# CryptoBoard.net
KiCad netlist of a schematic drawn in EAGLE
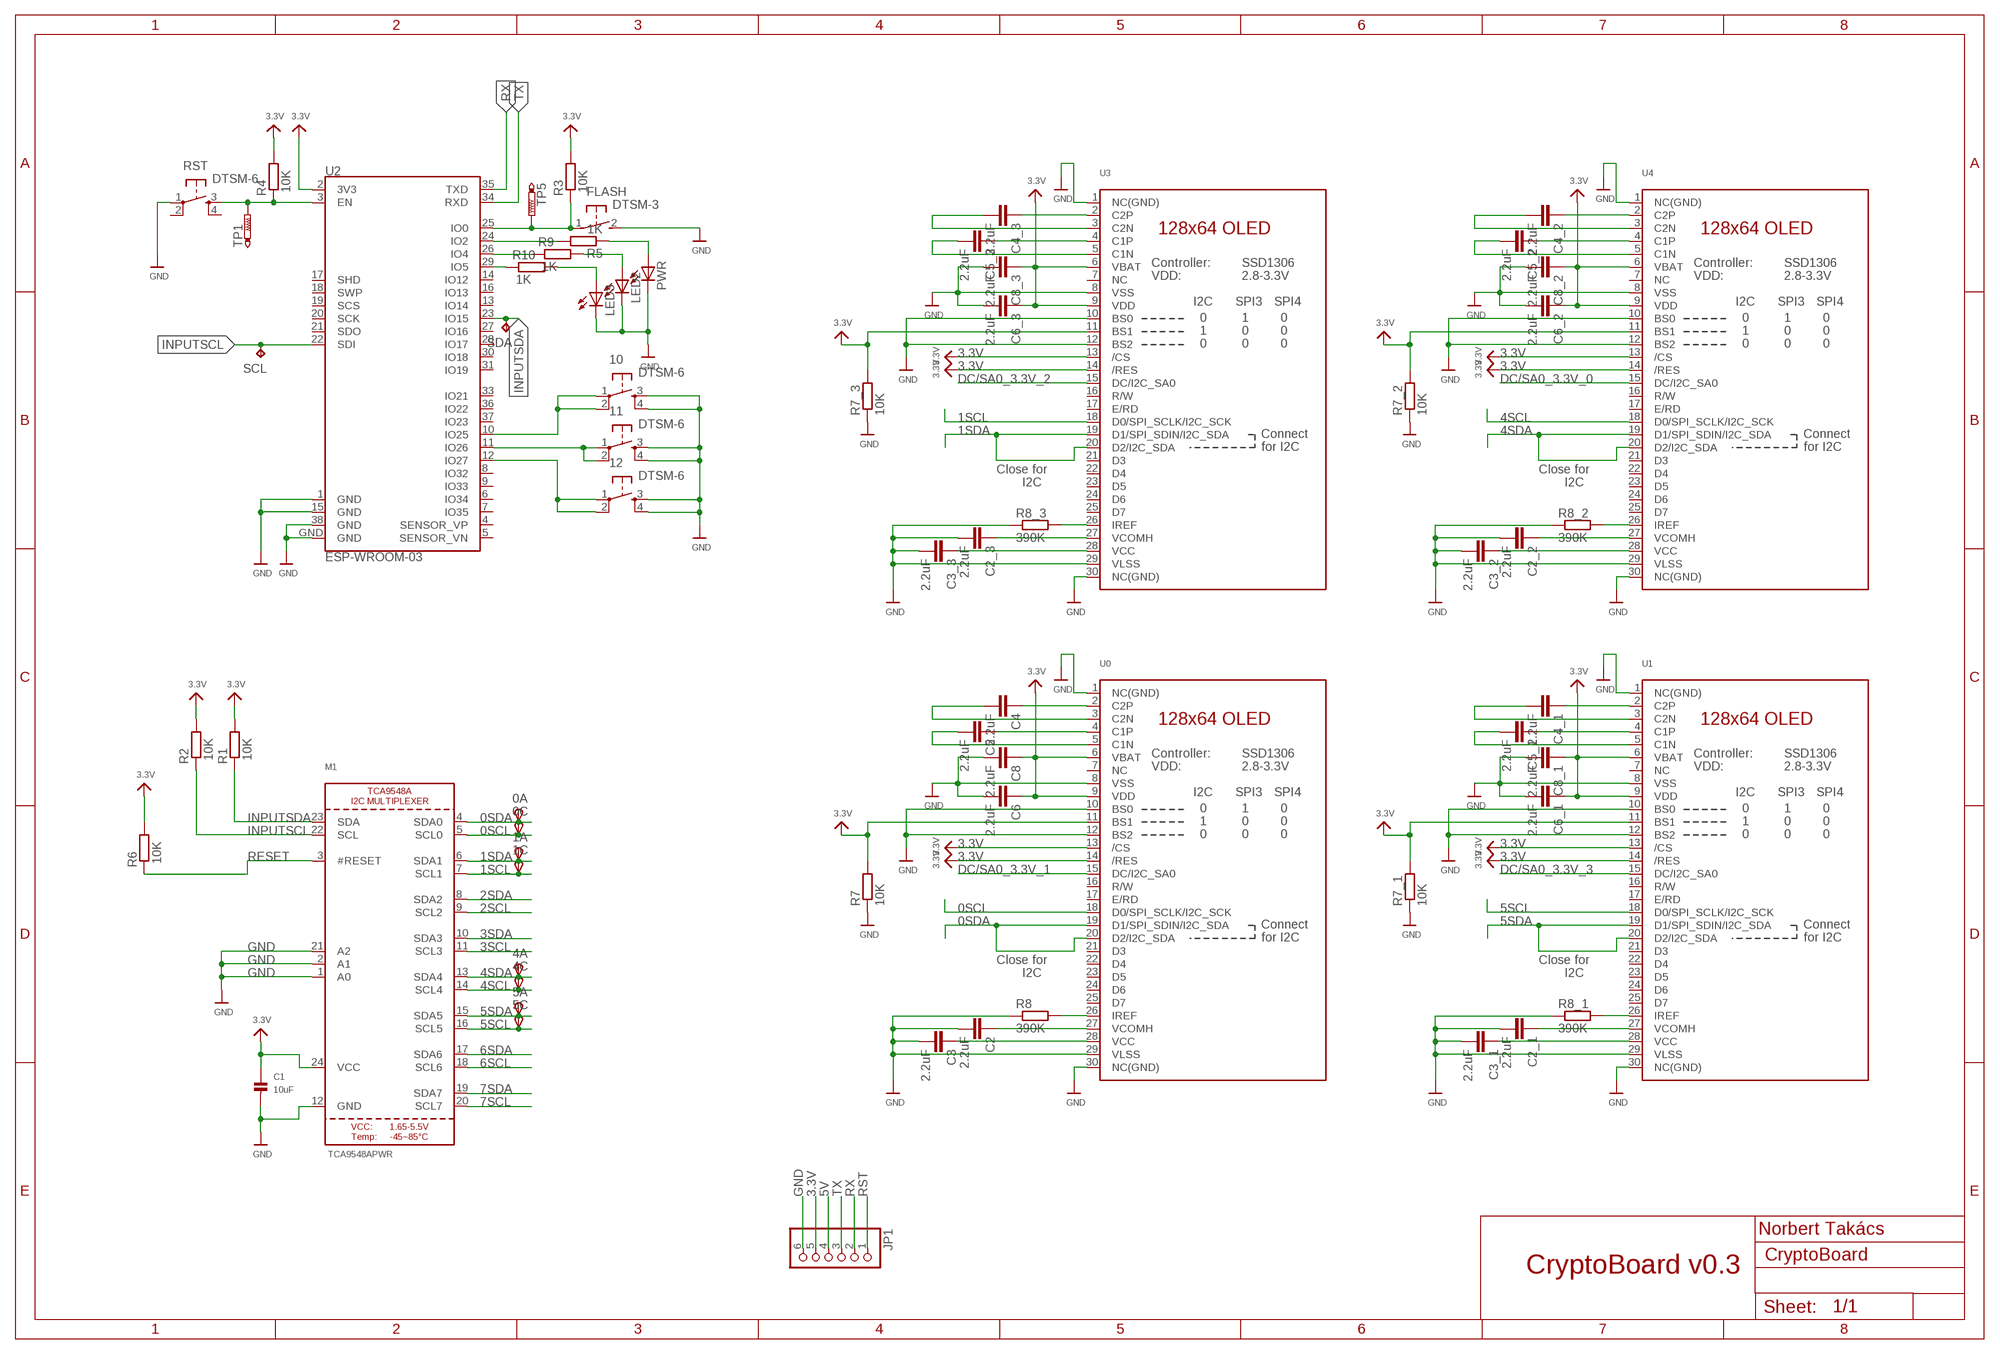
[diagram p0: schematic, sheet 1]

(export (version "E")
  (design (tool "Eeschema 10.0.6"))
  (components
    (comp (ref "0A")
      (value "TPSTP20R")
      (footprint "eagle-import:TP20R")
      (libsource (lib "eagle-import") (part "TPSTP20R"))
    )
    (comp (ref "0C")
      (value "TPSTP20R")
      (footprint "eagle-import:TP20R")
      (libsource (lib "eagle-import") (part "TPSTP20R"))
    )
    (comp (ref "1A")
      (value "TPSTP20R")
      (footprint "eagle-import:TP20R")
      (libsource (lib "eagle-import") (part "TPSTP20R"))
    )
    (comp (ref "1C")
      (value "TPSTP20R")
      (footprint "eagle-import:TP20R")
      (libsource (lib "eagle-import") (part "TPSTP20R"))
    )
    (comp (ref "4A")
      (value "TPSTP20R")
      (footprint "eagle-import:TP20R")
      (libsource (lib "eagle-import") (part "TPSTP20R"))
    )
    (comp (ref "4C")
      (value "TPSTP20R")
      (footprint "eagle-import:TP20R")
      (libsource (lib "eagle-import") (part "TPSTP20R"))
    )
    (comp (ref "5A")
      (value "TPSTP20R")
      (footprint "eagle-import:TP20R")
      (libsource (lib "eagle-import") (part "TPSTP20R"))
    )
    (comp (ref "5C")
      (value "TPSTP20R")
      (footprint "eagle-import:TP20R")
      (libsource (lib "eagle-import") (part "TPSTP20R"))
    )
    (comp (ref "10")
      (value "DTSM-6")
      (footprint "eagle-import:DTSM-6")
      (libsource (lib "eagle-import") (part "DTSM-6"))
    )
    (comp (ref "11")
      (value "DTSM-6")
      (footprint "eagle-import:DTSM-6")
      (libsource (lib "eagle-import") (part "DTSM-6"))
    )
    (comp (ref "12")
      (value "DTSM-6")
      (footprint "eagle-import:DTSM-6")
      (libsource (lib "eagle-import") (part "DTSM-6"))
    )
    (comp (ref "C1")
      (value "10uF")
      (footprint "eagle-import:0805")
      (libsource (lib "eagle-import") (part "CAP_CERAMIC0805"))
    )
    (comp (ref "C2")
      (value "2.2uF")
      (footprint "eagle-import:C0805")
      (libsource (lib "eagle-import") (part "C-EUC0805"))
    )
    (comp (ref "C2_1")
      (value "2.2uF")
      (footprint "eagle-import:C0805")
      (libsource (lib "eagle-import") (part "C-EUC0805"))
    )
    (comp (ref "C2_2")
      (value "2.2uF")
      (footprint "eagle-import:C0805")
      (libsource (lib "eagle-import") (part "C-EUC0805"))
    )
    (comp (ref "C2_3")
      (value "2.2uF")
      (footprint "eagle-import:C0805")
      (libsource (lib "eagle-import") (part "C-EUC0805"))
    )
    (comp (ref "C3")
      (value "2.2uF")
      (footprint "eagle-import:C0805")
      (libsource (lib "eagle-import") (part "C-EUC0805"))
    )
    (comp (ref "C3_1")
      (value "2.2uF")
      (footprint "eagle-import:C0805")
      (libsource (lib "eagle-import") (part "C-EUC0805"))
    )
    (comp (ref "C3_2")
      (value "2.2uF")
      (footprint "eagle-import:C0805")
      (libsource (lib "eagle-import") (part "C-EUC0805"))
    )
    (comp (ref "C3_3")
      (value "2.2uF")
      (footprint "eagle-import:C0805")
      (libsource (lib "eagle-import") (part "C-EUC0805"))
    )
    (comp (ref "C4")
      (value "2.2uF")
      (footprint "eagle-import:C0805")
      (libsource (lib "eagle-import") (part "C-EUC0805"))
    )
    (comp (ref "C4_1")
      (value "2.2uF")
      (footprint "eagle-import:C0805")
      (libsource (lib "eagle-import") (part "C-EUC0805"))
    )
    (comp (ref "C4_2")
      (value "2.2uF")
      (footprint "eagle-import:C0805")
      (libsource (lib "eagle-import") (part "C-EUC0805"))
    )
    (comp (ref "C4_3")
      (value "2.2uF")
      (footprint "eagle-import:C0805")
      (libsource (lib "eagle-import") (part "C-EUC0805"))
    )
    (comp (ref "C5")
      (value "2.2uF")
      (footprint "eagle-import:C0805")
      (libsource (lib "eagle-import") (part "C-EUC0805"))
    )
    (comp (ref "C5_1")
      (value "2.2uF")
      (footprint "eagle-import:C0805")
      (libsource (lib "eagle-import") (part "C-EUC0805"))
    )
    (comp (ref "C5_2")
      (value "2.2uF")
      (footprint "eagle-import:C0805")
      (libsource (lib "eagle-import") (part "C-EUC0805"))
    )
    (comp (ref "C5_3")
      (value "2.2uF")
      (footprint "eagle-import:C0805")
      (libsource (lib "eagle-import") (part "C-EUC0805"))
    )
    (comp (ref "C6")
      (value "2.2uF")
      (footprint "eagle-import:C0805")
      (libsource (lib "eagle-import") (part "C-EUC0805"))
    )
    (comp (ref "C6_1")
      (value "2.2uF")
      (footprint "eagle-import:C0805")
      (libsource (lib "eagle-import") (part "C-EUC0805"))
    )
    (comp (ref "C6_2")
      (value "2.2uF")
      (footprint "eagle-import:C0805")
      (libsource (lib "eagle-import") (part "C-EUC0805"))
    )
    (comp (ref "C6_3")
      (value "2.2uF")
      (footprint "eagle-import:C0805")
      (libsource (lib "eagle-import") (part "C-EUC0805"))
    )
    (comp (ref "C8")
      (value "2.2uF")
      (footprint "eagle-import:C0805")
      (libsource (lib "eagle-import") (part "C-EUC0805"))
    )
    (comp (ref "C8_1")
      (value "2.2uF")
      (footprint "eagle-import:C0805")
      (libsource (lib "eagle-import") (part "C-EUC0805"))
    )
    (comp (ref "C8_2")
      (value "2.2uF")
      (footprint "eagle-import:C0805")
      (libsource (lib "eagle-import") (part "C-EUC0805"))
    )
    (comp (ref "C8_3")
      (value "2.2uF")
      (footprint "eagle-import:C0805")
      (libsource (lib "eagle-import") (part "C-EUC0805"))
    )
    (comp (ref "FLASH")
      (value "DTSM-3")
      (footprint "eagle-import:DTSM-3")
      (libsource (lib "eagle-import") (part "DTSM-3"))
    )
    (comp (ref "JP1")
      (value "PINHD-1X6")
      (footprint "eagle-import:1X06")
      (libsource (lib "eagle-import") (part "PINHD-1X6"))
    )
    (comp (ref "LED2")
      (value "LEDSML0805")
      (footprint "eagle-import:SML0805")
      (libsource (lib "eagle-import") (part "LEDSML0805"))
    )
    (comp (ref "LED3")
      (value "LEDSML0805")
      (footprint "eagle-import:SML0805")
      (libsource (lib "eagle-import") (part "LEDSML0805"))
    )
    (comp (ref "M1")
      (value "TCA9548APWR")
      (footprint "eagle-import:TSSOP24")
      (libsource (lib "eagle-import") (part "TCA9548A"))
    )
    (comp (ref "PWR")
      (value "LEDSML0805")
      (footprint "eagle-import:SML0805")
      (libsource (lib "eagle-import") (part "LEDSML0805"))
    )
    (comp (ref "R1")
      (value "10K")
      (footprint "eagle-import:M0805")
      (libsource (lib "eagle-import") (part "R-EU_M0805"))
    )
    (comp (ref "R2")
      (value "10K")
      (footprint "eagle-import:M0805")
      (libsource (lib "eagle-import") (part "R-EU_M0805"))
    )
    (comp (ref "R3")
      (value "10K")
      (footprint "eagle-import:M0805")
      (libsource (lib "eagle-import") (part "R-EU_M0805"))
    )
    (comp (ref "R4")
      (value "10K")
      (footprint "eagle-import:M0805")
      (libsource (lib "eagle-import") (part "R-EU_M0805"))
    )
    (comp (ref "R5")
      (value "1K")
      (footprint "eagle-import:M0805")
      (libsource (lib "eagle-import") (part "R-EU_M0805"))
    )
    (comp (ref "R6")
      (value "10K")
      (footprint "eagle-import:M0805")
      (libsource (lib "eagle-import") (part "R-EU_M0805"))
    )
    (comp (ref "R7")
      (value "10K")
      (footprint "eagle-import:M0805")
      (libsource (lib "eagle-import") (part "R-EU_M0805"))
    )
    (comp (ref "R7_1")
      (value "10K")
      (footprint "eagle-import:M0805")
      (libsource (lib "eagle-import") (part "R-EU_M0805"))
    )
    (comp (ref "R7_2")
      (value "10K")
      (footprint "eagle-import:M0805")
      (libsource (lib "eagle-import") (part "R-EU_M0805"))
    )
    (comp (ref "R7_3")
      (value "10K")
      (footprint "eagle-import:M0805")
      (libsource (lib "eagle-import") (part "R-EU_M0805"))
    )
    (comp (ref "R8")
      (value "390K")
      (footprint "eagle-import:M0805")
      (libsource (lib "eagle-import") (part "R-EU_M0805"))
    )
    (comp (ref "R8_1")
      (value "390K")
      (footprint "eagle-import:M0805")
      (libsource (lib "eagle-import") (part "R-EU_M0805"))
    )
    (comp (ref "R8_2")
      (value "390K")
      (footprint "eagle-import:M0805")
      (libsource (lib "eagle-import") (part "R-EU_M0805"))
    )
    (comp (ref "R8_3")
      (value "390K")
      (footprint "eagle-import:M0805")
      (libsource (lib "eagle-import") (part "R-EU_M0805"))
    )
    (comp (ref "R9")
      (value "1K")
      (footprint "eagle-import:M0805")
      (libsource (lib "eagle-import") (part "R-EU_M0805"))
    )
    (comp (ref "R10")
      (value "1K")
      (footprint "eagle-import:M0805")
      (libsource (lib "eagle-import") (part "R-EU_M0805"))
    )
    (comp (ref "RST")
      (value "DTSM-6")
      (footprint "eagle-import:DTSM-6")
      (libsource (lib "eagle-import") (part "DTSM-6"))
    )
    (comp (ref "SCL")
      (value "TPPAD1-13")
      (footprint "eagle-import:P1-13")
      (libsource (lib "eagle-import") (part "TPPAD1-13"))
    )
    (comp (ref "SDA")
      (value "TPPAD1-13")
      (footprint "eagle-import:P1-13")
      (libsource (lib "eagle-import") (part "TPPAD1-13"))
    )
    (comp (ref "TP1")
      (value "PTR1B2,54")
      (footprint "eagle-import:B2,54")
      (libsource (lib "eagle-import") (part "PTR1B2,54"))
    )
    (comp (ref "TP5")
      (value "PTR1B2,54")
      (footprint "eagle-import:B2,54")
      (libsource (lib "eagle-import") (part "PTR1B2,54"))
    )
    (comp (ref "U0")
      (value "DISP_OLED_UG-2864HSWEG01")
      (footprint "eagle-import:UG-2864HSWEG01_1.3_WRAPAROUND")
      (libsource (lib "eagle-import") (part "DISP_OLED_UG-2864HSWEG01"))
    )
    (comp (ref "U1")
      (value "DISP_OLED_UG-2864HSWEG01")
      (footprint "eagle-import:UG-2864HSWEG01_1.3_WRAPAROUND")
      (libsource (lib "eagle-import") (part "DISP_OLED_UG-2864HSWEG01"))
    )
    (comp (ref "U2")
      (value "ESP-WROOM-03")
      (footprint "eagle-import:ESP-WROOM-03")
      (libsource (lib "eagle-import") (part "ESP-WROOM-03"))
    )
    (comp (ref "U3")
      (value "DISP_OLED_UG-2864HSWEG01")
      (footprint "eagle-import:UG-2864HSWEG01_1.3_WRAPAROUND")
      (libsource (lib "eagle-import") (part "DISP_OLED_UG-2864HSWEG01"))
    )
    (comp (ref "U4")
      (value "DISP_OLED_UG-2864HSWEG01")
      (footprint "eagle-import:UG-2864HSWEG01_1.3_WRAPAROUND")
      (libsource (lib "eagle-import") (part "DISP_OLED_UG-2864HSWEG01"))
    )
  )
  (nets
    (net (code "1") (name "/0SCL") (class "Default")
      (node (ref "0C") (pin "TP") (pinfunction "PP_TP") (pintype "input"))
      (node (ref "M1") (pin "5") (pinfunction "SCL0_5") (pintype "bidirectional"))
      (node (ref "U0") (pin "18") (pinfunction "D0/SPI_SCLK/I2C_SCK_18") (pintype "bidirectional"))
    )
    (net (code "2") (name "/0SDA") (class "Default")
      (node (ref "0A") (pin "TP") (pinfunction "PP_TP") (pintype "input"))
      (node (ref "M1") (pin "4") (pinfunction "SDA0_4") (pintype "bidirectional"))
      (node (ref "U0") (pin "19") (pinfunction "D1/SPI_SDIN/I2C_SDA_19") (pintype "bidirectional"))
      (node (ref "U0") (pin "20") (pinfunction "D2/I2C_SDA_20") (pintype "bidirectional"))
    )
    (net (code "3") (name "/1SCL") (class "Default")
      (node (ref "1C") (pin "TP") (pinfunction "PP_TP") (pintype "input"))
      (node (ref "M1") (pin "7") (pinfunction "SCL1_7") (pintype "bidirectional"))
      (node (ref "U3") (pin "18") (pinfunction "D0/SPI_SCLK/I2C_SCK_18") (pintype "bidirectional"))
    )
    (net (code "4") (name "/1SDA") (class "Default")
      (node (ref "1A") (pin "TP") (pinfunction "PP_TP") (pintype "input"))
      (node (ref "M1") (pin "6") (pinfunction "SDA1_6") (pintype "bidirectional"))
      (node (ref "U3") (pin "19") (pinfunction "D1/SPI_SDIN/I2C_SDA_19") (pintype "bidirectional"))
      (node (ref "U3") (pin "20") (pinfunction "D2/I2C_SDA_20") (pintype "bidirectional"))
    )
    (net (code "5") (name "/2SCL") (class "Default")
      (node (ref "M1") (pin "9") (pinfunction "SCL2_9") (pintype "bidirectional"))
    )
    (net (code "6") (name "/2SDA") (class "Default")
      (node (ref "M1") (pin "8") (pinfunction "SDA2_8") (pintype "bidirectional"))
    )
    (net (code "7") (name "/3SCL") (class "Default")
      (node (ref "M1") (pin "11") (pinfunction "SCL3_11") (pintype "bidirectional"))
    )
    (net (code "8") (name "/3SDA") (class "Default")
      (node (ref "M1") (pin "10") (pinfunction "SDA3_10") (pintype "bidirectional"))
    )
    (net (code "9") (name "/4SCL") (class "Default")
      (node (ref "4C") (pin "TP") (pinfunction "PP_TP") (pintype "input"))
      (node (ref "M1") (pin "14") (pinfunction "SCL4_14") (pintype "bidirectional"))
      (node (ref "U4") (pin "18") (pinfunction "D0/SPI_SCLK/I2C_SCK_18") (pintype "bidirectional"))
    )
    (net (code "10") (name "/4SDA") (class "Default")
      (node (ref "4A") (pin "TP") (pinfunction "PP_TP") (pintype "input"))
      (node (ref "M1") (pin "13") (pinfunction "SDA4_13") (pintype "bidirectional"))
      (node (ref "U4") (pin "19") (pinfunction "D1/SPI_SDIN/I2C_SDA_19") (pintype "bidirectional"))
      (node (ref "U4") (pin "20") (pinfunction "D2/I2C_SDA_20") (pintype "bidirectional"))
    )
    (net (code "11") (name "/5SCL") (class "Default")
      (node (ref "5C") (pin "TP") (pinfunction "PP_TP") (pintype "input"))
      (node (ref "M1") (pin "16") (pinfunction "SCL5_16") (pintype "bidirectional"))
      (node (ref "U1") (pin "18") (pinfunction "D0/SPI_SCLK/I2C_SCK_18") (pintype "bidirectional"))
    )
    (net (code "12") (name "/5SDA") (class "Default")
      (node (ref "5A") (pin "TP") (pinfunction "PP_TP") (pintype "input"))
      (node (ref "M1") (pin "15") (pinfunction "SDA5_15") (pintype "bidirectional"))
      (node (ref "U1") (pin "19") (pinfunction "D1/SPI_SDIN/I2C_SDA_19") (pintype "bidirectional"))
      (node (ref "U1") (pin "20") (pinfunction "D2/I2C_SDA_20") (pintype "bidirectional"))
    )
    (net (code "13") (name "/5V") (class "Default")
      (node (ref "JP1") (pin "4") (pinfunction "4_4") (pintype "passive"))
    )
    (net (code "14") (name "/6SCL") (class "Default")
      (node (ref "M1") (pin "18") (pinfunction "SCL6_18") (pintype "bidirectional"))
    )
    (net (code "15") (name "/6SDA") (class "Default")
      (node (ref "M1") (pin "17") (pinfunction "SDA6_17") (pintype "bidirectional"))
    )
    (net (code "16") (name "/7SCL") (class "Default")
      (node (ref "M1") (pin "20") (pinfunction "SCL7_20") (pintype "bidirectional"))
    )
    (net (code "17") (name "/7SDA") (class "Default")
      (node (ref "M1") (pin "19") (pinfunction "SDA7_19") (pintype "bidirectional"))
    )
    (net (code "18") (name "/DC{slash}SA0_3.3V_0") (class "Default")
      (node (ref "U4") (pin "15") (pinfunction "DC/I2C_SA0_15") (pintype "input"))
    )
    (net (code "19") (name "/DC{slash}SA0_3.3V_1") (class "Default")
      (node (ref "U0") (pin "15") (pinfunction "DC/I2C_SA0_15") (pintype "input"))
    )
    (net (code "20") (name "/DC{slash}SA0_3.3V_2") (class "Default")
      (node (ref "U3") (pin "15") (pinfunction "DC/I2C_SA0_15") (pintype "input"))
    )
    (net (code "21") (name "/DC{slash}SA0_3.3V_3") (class "Default")
      (node (ref "U1") (pin "15") (pinfunction "DC/I2C_SA0_15") (pintype "input"))
    )
    (net (code "22") (name "/RESET") (class "Default")
      (node (ref "M1") (pin "3") (pinfunction "#RESET_3") (pintype "bidirectional"))
      (node (ref "R6") (pin "1") (pinfunction "1_1") (pintype "passive"))
    )
    (net (code "23") (name "/RST") (class "Default")
      (node (ref "JP1") (pin "1") (pinfunction "1_1") (pintype "passive"))
    )
    (net (code "24") (name "3.3V") (class "Default")
      (node (ref "C1") (pin "1") (pinfunction "P$1_1") (pintype "passive"))
      (node (ref "C6") (pin "1") (pinfunction "1_1") (pintype "passive"))
      (node (ref "C6_1") (pin "1") (pinfunction "1_1") (pintype "passive"))
      (node (ref "C6_2") (pin "1") (pinfunction "1_1") (pintype "passive"))
      (node (ref "C6_3") (pin "1") (pinfunction "1_1") (pintype "passive"))
      (node (ref "C8") (pin "1") (pinfunction "1_1") (pintype "passive"))
      (node (ref "C8_1") (pin "1") (pinfunction "1_1") (pintype "passive"))
      (node (ref "C8_2") (pin "1") (pinfunction "1_1") (pintype "passive"))
      (node (ref "C8_3") (pin "1") (pinfunction "1_1") (pintype "passive"))
      (node (ref "JP1") (pin "5") (pinfunction "5_5") (pintype "passive"))
      (node (ref "M1") (pin "24") (pinfunction "VCC_24") (pintype "bidirectional"))
      (node (ref "R1") (pin "2") (pinfunction "2_2") (pintype "passive"))
      (node (ref "R2") (pin "2") (pinfunction "2_2") (pintype "passive"))
      (node (ref "R3") (pin "2") (pinfunction "2_2") (pintype "passive"))
      (node (ref "R4") (pin "2") (pinfunction "2_2") (pintype "passive"))
      (node (ref "R6") (pin "2") (pinfunction "2_2") (pintype "passive"))
      (node (ref "R7") (pin "2") (pinfunction "2_2") (pintype "passive"))
      (node (ref "R7_1") (pin "2") (pinfunction "2_2") (pintype "passive"))
      (node (ref "R7_2") (pin "2") (pinfunction "2_2") (pintype "passive"))
      (node (ref "R7_3") (pin "2") (pinfunction "2_2") (pintype "passive"))
      (node (ref "U0") (pin "11") (pinfunction "BS1_11") (pintype "input"))
      (node (ref "U0") (pin "13") (pinfunction "/CS_13") (pintype "input"))
      (node (ref "U0") (pin "14") (pinfunction "/RES_14") (pintype "input"))
      (node (ref "U0") (pin "6") (pinfunction "VBAT_6") (pintype "input"))
      (node (ref "U0") (pin "9") (pinfunction "VDD_9") (pintype "power_in"))
      (node (ref "U1") (pin "11") (pinfunction "BS1_11") (pintype "input"))
      (node (ref "U1") (pin "13") (pinfunction "/CS_13") (pintype "input"))
      (node (ref "U1") (pin "14") (pinfunction "/RES_14") (pintype "input"))
      (node (ref "U1") (pin "6") (pinfunction "VBAT_6") (pintype "input"))
      (node (ref "U1") (pin "9") (pinfunction "VDD_9") (pintype "power_in"))
      (node (ref "U2") (pin "2") (pinfunction "3V3_2") (pintype "bidirectional"))
      (node (ref "U3") (pin "11") (pinfunction "BS1_11") (pintype "input"))
      (node (ref "U3") (pin "13") (pinfunction "/CS_13") (pintype "input"))
      (node (ref "U3") (pin "14") (pinfunction "/RES_14") (pintype "input"))
      (node (ref "U3") (pin "6") (pinfunction "VBAT_6") (pintype "input"))
      (node (ref "U3") (pin "9") (pinfunction "VDD_9") (pintype "power_in"))
      (node (ref "U4") (pin "11") (pinfunction "BS1_11") (pintype "input"))
      (node (ref "U4") (pin "13") (pinfunction "/CS_13") (pintype "input"))
      (node (ref "U4") (pin "14") (pinfunction "/RES_14") (pintype "input"))
      (node (ref "U4") (pin "6") (pinfunction "VBAT_6") (pintype "input"))
      (node (ref "U4") (pin "9") (pinfunction "VDD_9") (pintype "power_in"))
    )
    (net (code "25") (name "GND") (class "Default")
      (node (ref "10") (pin "3") (pinfunction "3_3") (pintype "passive"))
      (node (ref "10") (pin "4") (pinfunction "4_4") (pintype "passive"))
      (node (ref "11") (pin "3") (pinfunction "3_3") (pintype "passive"))
      (node (ref "11") (pin "4") (pinfunction "4_4") (pintype "passive"))
      (node (ref "12") (pin "3") (pinfunction "3_3") (pintype "passive"))
      (node (ref "12") (pin "4") (pinfunction "4_4") (pintype "passive"))
      (node (ref "C1") (pin "2") (pinfunction "P$2_2") (pintype "passive"))
      (node (ref "C2") (pin "2") (pinfunction "2_2") (pintype "passive"))
      (node (ref "C2_1") (pin "2") (pinfunction "2_2") (pintype "passive"))
      (node (ref "C2_2") (pin "2") (pinfunction "2_2") (pintype "passive"))
      (node (ref "C2_3") (pin "2") (pinfunction "2_2") (pintype "passive"))
      (node (ref "C3") (pin "2") (pinfunction "2_2") (pintype "passive"))
      (node (ref "C3_1") (pin "2") (pinfunction "2_2") (pintype "passive"))
      (node (ref "C3_2") (pin "2") (pinfunction "2_2") (pintype "passive"))
      (node (ref "C3_3") (pin "2") (pinfunction "2_2") (pintype "passive"))
      (node (ref "C6") (pin "2") (pinfunction "2_2") (pintype "passive"))
      (node (ref "C6_1") (pin "2") (pinfunction "2_2") (pintype "passive"))
      (node (ref "C6_2") (pin "2") (pinfunction "2_2") (pintype "passive"))
      (node (ref "C6_3") (pin "2") (pinfunction "2_2") (pintype "passive"))
      (node (ref "C8") (pin "2") (pinfunction "2_2") (pintype "passive"))
      (node (ref "C8_1") (pin "2") (pinfunction "2_2") (pintype "passive"))
      (node (ref "C8_2") (pin "2") (pinfunction "2_2") (pintype "passive"))
      (node (ref "C8_3") (pin "2") (pinfunction "2_2") (pintype "passive"))
      (node (ref "FLASH") (pin "2") (pinfunction "2_2") (pintype "passive"))
      (node (ref "JP1") (pin "6") (pinfunction "6_6") (pintype "passive"))
      (node (ref "LED2") (pin "C") (pinfunction "C_C") (pintype "passive"))
      (node (ref "LED3") (pin "C") (pinfunction "C_C") (pintype "passive"))
      (node (ref "M1") (pin "1") (pinfunction "A0_1") (pintype "bidirectional"))
      (node (ref "M1") (pin "12") (pinfunction "GND_12") (pintype "bidirectional"))
      (node (ref "M1") (pin "2") (pinfunction "A1_2") (pintype "bidirectional"))
      (node (ref "M1") (pin "21") (pinfunction "A2_21") (pintype "bidirectional"))
      (node (ref "PWR") (pin "C") (pinfunction "C_C") (pintype "passive"))
      (node (ref "R7") (pin "1") (pinfunction "1_1") (pintype "passive"))
      (node (ref "R7_1") (pin "1") (pinfunction "1_1") (pintype "passive"))
      (node (ref "R7_2") (pin "1") (pinfunction "1_1") (pintype "passive"))
      (node (ref "R7_3") (pin "1") (pinfunction "1_1") (pintype "passive"))
      (node (ref "R8") (pin "1") (pinfunction "1_1") (pintype "passive"))
      (node (ref "R8_1") (pin "1") (pinfunction "1_1") (pintype "passive"))
      (node (ref "R8_2") (pin "1") (pinfunction "1_1") (pintype "passive"))
      (node (ref "R8_3") (pin "1") (pinfunction "1_1") (pintype "passive"))
      (node (ref "RST") (pin "1") (pinfunction "1_1") (pintype "passive"))
      (node (ref "U0") (pin "1") (pinfunction "NC(GND)_1") (pintype "input"))
      (node (ref "U0") (pin "10") (pinfunction "BS0_10") (pintype "input"))
      (node (ref "U0") (pin "12") (pinfunction "BS2_12") (pintype "input"))
      (node (ref "U0") (pin "29") (pinfunction "VLSS_29") (pintype "power_in"))
      (node (ref "U0") (pin "30") (pinfunction "NC(GND)_30") (pintype "input"))
      (node (ref "U0") (pin "8") (pinfunction "VSS_8") (pintype "power_in"))
      (node (ref "U1") (pin "1") (pinfunction "NC(GND)_1") (pintype "input"))
      (node (ref "U1") (pin "10") (pinfunction "BS0_10") (pintype "input"))
      (node (ref "U1") (pin "12") (pinfunction "BS2_12") (pintype "input"))
      (node (ref "U1") (pin "29") (pinfunction "VLSS_29") (pintype "power_in"))
      (node (ref "U1") (pin "30") (pinfunction "NC(GND)_30") (pintype "input"))
      (node (ref "U1") (pin "8") (pinfunction "VSS_8") (pintype "power_in"))
      (node (ref "U2") (pin "1") (pinfunction "GND_1") (pintype "bidirectional"))
      (node (ref "U2") (pin "15") (pinfunction "GND_15") (pintype "bidirectional"))
      (node (ref "U2") (pin "38") (pinfunction "GND_38") (pintype "bidirectional"))
      (node (ref "U2") (pin "GND") (pinfunction "GND_GND") (pintype "bidirectional"))
      (node (ref "U3") (pin "1") (pinfunction "NC(GND)_1") (pintype "input"))
      (node (ref "U3") (pin "10") (pinfunction "BS0_10") (pintype "input"))
      (node (ref "U3") (pin "12") (pinfunction "BS2_12") (pintype "input"))
      (node (ref "U3") (pin "29") (pinfunction "VLSS_29") (pintype "power_in"))
      (node (ref "U3") (pin "30") (pinfunction "NC(GND)_30") (pintype "input"))
      (node (ref "U3") (pin "8") (pinfunction "VSS_8") (pintype "power_in"))
      (node (ref "U4") (pin "1") (pinfunction "NC(GND)_1") (pintype "input"))
      (node (ref "U4") (pin "10") (pinfunction "BS0_10") (pintype "input"))
      (node (ref "U4") (pin "12") (pinfunction "BS2_12") (pintype "input"))
      (node (ref "U4") (pin "29") (pinfunction "VLSS_29") (pintype "power_in"))
      (node (ref "U4") (pin "30") (pinfunction "NC(GND)_30") (pintype "input"))
      (node (ref "U4") (pin "8") (pinfunction "VSS_8") (pintype "power_in"))
    )
    (net (code "26") (name "INPUTSCL") (class "Default")
      (node (ref "M1") (pin "22") (pinfunction "SCL_22") (pintype "bidirectional"))
      (node (ref "R2") (pin "1") (pinfunction "1_1") (pintype "passive"))
      (node (ref "SCL") (pin "TP") (pinfunction "TP_TP") (pintype "input"))
      (node (ref "U2") (pin "22") (pinfunction "SDI_22") (pintype "bidirectional"))
    )
    (net (code "27") (name "INPUTSDA") (class "Default")
      (node (ref "M1") (pin "23") (pinfunction "SDA_23") (pintype "bidirectional"))
      (node (ref "R1") (pin "1") (pinfunction "1_1") (pintype "passive"))
      (node (ref "SDA") (pin "TP") (pinfunction "TP_TP") (pintype "input"))
      (node (ref "U2") (pin "23") (pinfunction "IO15_23") (pintype "bidirectional"))
    )
    (net (code "28") (name "Net-(LED2-PadA)") (class "Default")
      (node (ref "LED2") (pin "A") (pinfunction "A_A") (pintype "passive"))
      (node (ref "R9") (pin "2") (pinfunction "2_2") (pintype "passive"))
    )
    (net (code "29") (name "Net-(LED3-PadA)") (class "Default")
      (node (ref "LED3") (pin "A") (pinfunction "A_A") (pintype "passive"))
      (node (ref "R10") (pin "2") (pinfunction "2_2") (pintype "passive"))
    )
    (net (code "30") (name "Net-(PWR-PadA)") (class "Default")
      (node (ref "PWR") (pin "A") (pinfunction "A_A") (pintype "passive"))
      (node (ref "R5") (pin "1") (pinfunction "1_1") (pintype "passive"))
    )
    (net (code "31") (name "Net-(U0-C1N)") (class "Default")
      (node (ref "C5") (pin "2") (pinfunction "2_2") (pintype "passive"))
      (node (ref "U0") (pin "5") (pinfunction "C1N_5") (pintype "input"))
    )
    (net (code "32") (name "Net-(U0-C1P)") (class "Default")
      (node (ref "C5") (pin "1") (pinfunction "1_1") (pintype "passive"))
      (node (ref "U0") (pin "4") (pinfunction "C1P_4") (pintype "input"))
    )
    (net (code "33") (name "Net-(U0-C2N)") (class "Default")
      (node (ref "C4") (pin "2") (pinfunction "2_2") (pintype "passive"))
      (node (ref "U0") (pin "3") (pinfunction "C2N_3") (pintype "input"))
    )
    (net (code "34") (name "Net-(U0-C2P)") (class "Default")
      (node (ref "C4") (pin "1") (pinfunction "1_1") (pintype "passive"))
      (node (ref "U0") (pin "2") (pinfunction "C2P_2") (pintype "input"))
    )
    (net (code "35") (name "Net-(U0-IREF)") (class "Default")
      (node (ref "R8") (pin "2") (pinfunction "2_2") (pintype "passive"))
      (node (ref "U0") (pin "26") (pinfunction "IREF_26") (pintype "input"))
    )
    (net (code "36") (name "Net-(U0-VCC)") (class "Default")
      (node (ref "C3") (pin "1") (pinfunction "1_1") (pintype "passive"))
      (node (ref "U0") (pin "28") (pinfunction "VCC_28") (pintype "power_in"))
    )
    (net (code "37") (name "Net-(U0-VCOMH)") (class "Default")
      (node (ref "C2") (pin "1") (pinfunction "1_1") (pintype "passive"))
      (node (ref "U0") (pin "27") (pinfunction "VCOMH_27") (pintype "output"))
    )
    (net (code "38") (name "Net-(U1-C1N)") (class "Default")
      (node (ref "C5_1") (pin "2") (pinfunction "2_2") (pintype "passive"))
      (node (ref "U1") (pin "5") (pinfunction "C1N_5") (pintype "input"))
    )
    (net (code "39") (name "Net-(U1-C1P)") (class "Default")
      (node (ref "C5_1") (pin "1") (pinfunction "1_1") (pintype "passive"))
      (node (ref "U1") (pin "4") (pinfunction "C1P_4") (pintype "input"))
    )
    (net (code "40") (name "Net-(U1-C2N)") (class "Default")
      (node (ref "C4_1") (pin "2") (pinfunction "2_2") (pintype "passive"))
      (node (ref "U1") (pin "3") (pinfunction "C2N_3") (pintype "input"))
    )
    (net (code "41") (name "Net-(U1-C2P)") (class "Default")
      (node (ref "C4_1") (pin "1") (pinfunction "1_1") (pintype "passive"))
      (node (ref "U1") (pin "2") (pinfunction "C2P_2") (pintype "input"))
    )
    (net (code "42") (name "Net-(U1-IREF)") (class "Default")
      (node (ref "R8_1") (pin "2") (pinfunction "2_2") (pintype "passive"))
      (node (ref "U1") (pin "26") (pinfunction "IREF_26") (pintype "input"))
    )
    (net (code "43") (name "Net-(U1-VCC)") (class "Default")
      (node (ref "C3_1") (pin "1") (pinfunction "1_1") (pintype "passive"))
      (node (ref "U1") (pin "28") (pinfunction "VCC_28") (pintype "power_in"))
    )
    (net (code "44") (name "Net-(U1-VCOMH)") (class "Default")
      (node (ref "C2_1") (pin "1") (pinfunction "1_1") (pintype "passive"))
      (node (ref "U1") (pin "27") (pinfunction "VCOMH_27") (pintype "output"))
    )
    (net (code "45") (name "Net-(U2-EN)") (class "Default")
      (node (ref "R4") (pin "1") (pinfunction "1_1") (pintype "passive"))
      (node (ref "RST") (pin "3") (pinfunction "3_3") (pintype "passive"))
      (node (ref "TP1") (pin "TP") (pinfunction "TP_TP") (pintype "input"))
      (node (ref "U2") (pin "3") (pinfunction "EN_3") (pintype "bidirectional"))
    )
    (net (code "46") (name "Net-(U2-IO0)") (class "Default")
      (node (ref "FLASH") (pin "1") (pinfunction "1_1") (pintype "passive"))
      (node (ref "R3") (pin "1") (pinfunction "1_1") (pintype "passive"))
      (node (ref "TP5") (pin "TP") (pinfunction "TP_TP") (pintype "input"))
      (node (ref "U2") (pin "25") (pinfunction "IO0_25") (pintype "bidirectional"))
    )
    (net (code "47") (name "Net-(U2-IO2)") (class "Default")
      (node (ref "R5") (pin "2") (pinfunction "2_2") (pintype "passive"))
      (node (ref "U2") (pin "24") (pinfunction "IO2_24") (pintype "bidirectional"))
    )
    (net (code "48") (name "Net-(U2-IO4)") (class "Default")
      (node (ref "R9") (pin "1") (pinfunction "1_1") (pintype "passive"))
      (node (ref "U2") (pin "26") (pinfunction "IO4_26") (pintype "bidirectional"))
    )
    (net (code "49") (name "Net-(U2-IO5)") (class "Default")
      (node (ref "R10") (pin "1") (pinfunction "1_1") (pintype "passive"))
      (node (ref "U2") (pin "29") (pinfunction "IO5_29") (pintype "bidirectional"))
    )
    (net (code "50") (name "Net-(U2-IO25)") (class "Default")
      (node (ref "10") (pin "1") (pinfunction "1_1") (pintype "passive"))
      (node (ref "10") (pin "2") (pinfunction "2_2") (pintype "passive"))
      (node (ref "U2") (pin "10") (pinfunction "IO25_10") (pintype "bidirectional"))
    )
    (net (code "51") (name "Net-(U2-IO26)") (class "Default")
      (node (ref "11") (pin "1") (pinfunction "1_1") (pintype "passive"))
      (node (ref "11") (pin "2") (pinfunction "2_2") (pintype "passive"))
      (node (ref "U2") (pin "11") (pinfunction "IO26_11") (pintype "bidirectional"))
    )
    (net (code "52") (name "Net-(U2-IO27)") (class "Default")
      (node (ref "12") (pin "1") (pinfunction "1_1") (pintype "passive"))
      (node (ref "12") (pin "2") (pinfunction "2_2") (pintype "passive"))
      (node (ref "U2") (pin "12") (pinfunction "IO27_12") (pintype "bidirectional"))
    )
    (net (code "53") (name "Net-(U3-C1N)") (class "Default")
      (node (ref "C5_3") (pin "2") (pinfunction "2_2") (pintype "passive"))
      (node (ref "U3") (pin "5") (pinfunction "C1N_5") (pintype "input"))
    )
    (net (code "54") (name "Net-(U3-C1P)") (class "Default")
      (node (ref "C5_3") (pin "1") (pinfunction "1_1") (pintype "passive"))
      (node (ref "U3") (pin "4") (pinfunction "C1P_4") (pintype "input"))
    )
    (net (code "55") (name "Net-(U3-C2N)") (class "Default")
      (node (ref "C4_3") (pin "2") (pinfunction "2_2") (pintype "passive"))
      (node (ref "U3") (pin "3") (pinfunction "C2N_3") (pintype "input"))
    )
    (net (code "56") (name "Net-(U3-C2P)") (class "Default")
      (node (ref "C4_3") (pin "1") (pinfunction "1_1") (pintype "passive"))
      (node (ref "U3") (pin "2") (pinfunction "C2P_2") (pintype "input"))
    )
    (net (code "57") (name "Net-(U3-IREF)") (class "Default")
      (node (ref "R8_3") (pin "2") (pinfunction "2_2") (pintype "passive"))
      (node (ref "U3") (pin "26") (pinfunction "IREF_26") (pintype "input"))
    )
    (net (code "58") (name "Net-(U3-VCC)") (class "Default")
      (node (ref "C3_3") (pin "1") (pinfunction "1_1") (pintype "passive"))
      (node (ref "U3") (pin "28") (pinfunction "VCC_28") (pintype "power_in"))
    )
    (net (code "59") (name "Net-(U3-VCOMH)") (class "Default")
      (node (ref "C2_3") (pin "1") (pinfunction "1_1") (pintype "passive"))
      (node (ref "U3") (pin "27") (pinfunction "VCOMH_27") (pintype "output"))
    )
    (net (code "60") (name "Net-(U4-C1N)") (class "Default")
      (node (ref "C5_2") (pin "2") (pinfunction "2_2") (pintype "passive"))
      (node (ref "U4") (pin "5") (pinfunction "C1N_5") (pintype "input"))
    )
    (net (code "61") (name "Net-(U4-C1P)") (class "Default")
      (node (ref "C5_2") (pin "1") (pinfunction "1_1") (pintype "passive"))
      (node (ref "U4") (pin "4") (pinfunction "C1P_4") (pintype "input"))
    )
    (net (code "62") (name "Net-(U4-C2N)") (class "Default")
      (node (ref "C4_2") (pin "2") (pinfunction "2_2") (pintype "passive"))
      (node (ref "U4") (pin "3") (pinfunction "C2N_3") (pintype "input"))
    )
    (net (code "63") (name "Net-(U4-C2P)") (class "Default")
      (node (ref "C4_2") (pin "1") (pinfunction "1_1") (pintype "passive"))
      (node (ref "U4") (pin "2") (pinfunction "C2P_2") (pintype "input"))
    )
    (net (code "64") (name "Net-(U4-IREF)") (class "Default")
      (node (ref "R8_2") (pin "2") (pinfunction "2_2") (pintype "passive"))
      (node (ref "U4") (pin "26") (pinfunction "IREF_26") (pintype "input"))
    )
    (net (code "65") (name "Net-(U4-VCC)") (class "Default")
      (node (ref "C3_2") (pin "1") (pinfunction "1_1") (pintype "passive"))
      (node (ref "U4") (pin "28") (pinfunction "VCC_28") (pintype "power_in"))
    )
    (net (code "66") (name "Net-(U4-VCOMH)") (class "Default")
      (node (ref "C2_2") (pin "1") (pinfunction "1_1") (pintype "passive"))
      (node (ref "U4") (pin "27") (pinfunction "VCOMH_27") (pintype "output"))
    )
    (net (code "67") (name "RX") (class "Default")
      (node (ref "JP1") (pin "2") (pinfunction "2_2") (pintype "passive"))
      (node (ref "U2") (pin "35") (pinfunction "TXD_35") (pintype "bidirectional"))
    )
    (net (code "68") (name "TX") (class "Default")
      (node (ref "JP1") (pin "3") (pinfunction "3_3") (pintype "passive"))
      (node (ref "U2") (pin "34") (pinfunction "RXD_34") (pintype "bidirectional"))
    )
    (net (code "69") (name "unconnected-(RST-Pad2)") (class "Default")
      (node (ref "RST") (pin "2") (pinfunction "2_2") (pintype "passive"))
    )
    (net (code "70") (name "unconnected-(RST-Pad4)") (class "Default")
      (node (ref "RST") (pin "4") (pinfunction "4_4") (pintype "passive"))
    )
    (net (code "71") (name "unconnected-(U0-D3-Pad21)") (class "Default")
      (node (ref "U0") (pin "21") (pinfunction "D3_21") (pintype "bidirectional"))
    )
    (net (code "72") (name "unconnected-(U0-D4-Pad22)") (class "Default")
      (node (ref "U0") (pin "22") (pinfunction "D4_22") (pintype "bidirectional"))
    )
    (net (code "73") (name "unconnected-(U0-D5-Pad23)") (class "Default")
      (node (ref "U0") (pin "23") (pinfunction "D5_23") (pintype "bidirectional"))
    )
    (net (code "74") (name "unconnected-(U0-D6-Pad24)") (class "Default")
      (node (ref "U0") (pin "24") (pinfunction "D6_24") (pintype "bidirectional"))
    )
    (net (code "75") (name "unconnected-(U0-D7-Pad25)") (class "Default")
      (node (ref "U0") (pin "25") (pinfunction "D7_25") (pintype "bidirectional"))
    )
    (net (code "76") (name "unconnected-(U0-E{slash}RD-Pad17)") (class "Default")
      (node (ref "U0") (pin "17") (pinfunction "E/RD_17") (pintype "input"))
    )
    (net (code "77") (name "unconnected-(U0-NC-Pad7)") (class "Default")
      (node (ref "U0") (pin "7") (pinfunction "NC_7") (pintype "no_connect"))
    )
    (net (code "78") (name "unconnected-(U0-R{slash}W-Pad16)") (class "Default")
      (node (ref "U0") (pin "16") (pinfunction "R/W_16") (pintype "input"))
    )
    (net (code "79") (name "unconnected-(U1-D3-Pad21)") (class "Default")
      (node (ref "U1") (pin "21") (pinfunction "D3_21") (pintype "bidirectional"))
    )
    (net (code "80") (name "unconnected-(U1-D4-Pad22)") (class "Default")
      (node (ref "U1") (pin "22") (pinfunction "D4_22") (pintype "bidirectional"))
    )
    (net (code "81") (name "unconnected-(U1-D5-Pad23)") (class "Default")
      (node (ref "U1") (pin "23") (pinfunction "D5_23") (pintype "bidirectional"))
    )
    (net (code "82") (name "unconnected-(U1-D6-Pad24)") (class "Default")
      (node (ref "U1") (pin "24") (pinfunction "D6_24") (pintype "bidirectional"))
    )
    (net (code "83") (name "unconnected-(U1-D7-Pad25)") (class "Default")
      (node (ref "U1") (pin "25") (pinfunction "D7_25") (pintype "bidirectional"))
    )
    (net (code "84") (name "unconnected-(U1-E{slash}RD-Pad17)") (class "Default")
      (node (ref "U1") (pin "17") (pinfunction "E/RD_17") (pintype "input"))
    )
    (net (code "85") (name "unconnected-(U1-NC-Pad7)") (class "Default")
      (node (ref "U1") (pin "7") (pinfunction "NC_7") (pintype "no_connect"))
    )
    (net (code "86") (name "unconnected-(U1-R{slash}W-Pad16)") (class "Default")
      (node (ref "U1") (pin "16") (pinfunction "R/W_16") (pintype "input"))
    )
    (net (code "87") (name "unconnected-(U2-IO12-Pad14)") (class "Default")
      (node (ref "U2") (pin "14") (pinfunction "IO12_14") (pintype "bidirectional"))
    )
    (net (code "88") (name "unconnected-(U2-IO13-Pad16)") (class "Default")
      (node (ref "U2") (pin "16") (pinfunction "IO13_16") (pintype "bidirectional"))
    )
    (net (code "89") (name "unconnected-(U2-IO14-Pad13)") (class "Default")
      (node (ref "U2") (pin "13") (pinfunction "IO14_13") (pintype "bidirectional"))
    )
    (net (code "90") (name "unconnected-(U2-IO16-Pad27)") (class "Default")
      (node (ref "U2") (pin "27") (pinfunction "IO16_27") (pintype "bidirectional"))
    )
    (net (code "91") (name "unconnected-(U2-IO17-Pad28)") (class "Default")
      (node (ref "U2") (pin "28") (pinfunction "IO17_28") (pintype "bidirectional"))
    )
    (net (code "92") (name "unconnected-(U2-IO18-Pad30)") (class "Default")
      (node (ref "U2") (pin "30") (pinfunction "IO18_30") (pintype "bidirectional"))
    )
    (net (code "93") (name "unconnected-(U2-IO19-Pad31)") (class "Default")
      (node (ref "U2") (pin "31") (pinfunction "IO19_31") (pintype "bidirectional"))
    )
    (net (code "94") (name "unconnected-(U2-IO21-Pad33)") (class "Default")
      (node (ref "U2") (pin "33") (pinfunction "IO21_33") (pintype "bidirectional"))
    )
    (net (code "95") (name "unconnected-(U2-IO22-Pad36)") (class "Default")
      (node (ref "U2") (pin "36") (pinfunction "IO22_36") (pintype "bidirectional"))
    )
    (net (code "96") (name "unconnected-(U2-IO23-Pad37)") (class "Default")
      (node (ref "U2") (pin "37") (pinfunction "IO23_37") (pintype "bidirectional"))
    )
    (net (code "97") (name "unconnected-(U2-IO32-Pad8)") (class "Default")
      (node (ref "U2") (pin "8") (pinfunction "IO32_8") (pintype "bidirectional"))
    )
    (net (code "98") (name "unconnected-(U2-IO33-Pad9)") (class "Default")
      (node (ref "U2") (pin "9") (pinfunction "IO33_9") (pintype "bidirectional"))
    )
    (net (code "99") (name "unconnected-(U2-IO34-Pad6)") (class "Default")
      (node (ref "U2") (pin "6") (pinfunction "IO34_6") (pintype "bidirectional"))
    )
    (net (code "100") (name "unconnected-(U2-IO35-Pad7)") (class "Default")
      (node (ref "U2") (pin "7") (pinfunction "IO35_7") (pintype "bidirectional"))
    )
    (net (code "101") (name "unconnected-(U2-SCK-Pad20)") (class "Default")
      (node (ref "U2") (pin "20") (pinfunction "SCK_20") (pintype "bidirectional"))
    )
    (net (code "102") (name "unconnected-(U2-SCS-Pad19)") (class "Default")
      (node (ref "U2") (pin "19") (pinfunction "SCS_19") (pintype "bidirectional"))
    )
    (net (code "103") (name "unconnected-(U2-SDO-Pad21)") (class "Default")
      (node (ref "U2") (pin "21") (pinfunction "SDO_21") (pintype "bidirectional"))
    )
    (net (code "104") (name "unconnected-(U2-SENSOR_VN-Pad5)") (class "Default")
      (node (ref "U2") (pin "5") (pinfunction "SENSOR_VN_5") (pintype "bidirectional"))
    )
    (net (code "105") (name "unconnected-(U2-SENSOR_VP-Pad4)") (class "Default")
      (node (ref "U2") (pin "4") (pinfunction "SENSOR_VP_4") (pintype "bidirectional"))
    )
    (net (code "106") (name "unconnected-(U2-SHD-Pad17)") (class "Default")
      (node (ref "U2") (pin "17") (pinfunction "SHD_17") (pintype "bidirectional"))
    )
    (net (code "107") (name "unconnected-(U2-SWP-Pad18)") (class "Default")
      (node (ref "U2") (pin "18") (pinfunction "SWP_18") (pintype "bidirectional"))
    )
    (net (code "108") (name "unconnected-(U3-D3-Pad21)") (class "Default")
      (node (ref "U3") (pin "21") (pinfunction "D3_21") (pintype "bidirectional"))
    )
    (net (code "109") (name "unconnected-(U3-D4-Pad22)") (class "Default")
      (node (ref "U3") (pin "22") (pinfunction "D4_22") (pintype "bidirectional"))
    )
    (net (code "110") (name "unconnected-(U3-D5-Pad23)") (class "Default")
      (node (ref "U3") (pin "23") (pinfunction "D5_23") (pintype "bidirectional"))
    )
    (net (code "111") (name "unconnected-(U3-D6-Pad24)") (class "Default")
      (node (ref "U3") (pin "24") (pinfunction "D6_24") (pintype "bidirectional"))
    )
    (net (code "112") (name "unconnected-(U3-D7-Pad25)") (class "Default")
      (node (ref "U3") (pin "25") (pinfunction "D7_25") (pintype "bidirectional"))
    )
    (net (code "113") (name "unconnected-(U3-E{slash}RD-Pad17)") (class "Default")
      (node (ref "U3") (pin "17") (pinfunction "E/RD_17") (pintype "input"))
    )
    (net (code "114") (name "unconnected-(U3-NC-Pad7)") (class "Default")
      (node (ref "U3") (pin "7") (pinfunction "NC_7") (pintype "no_connect"))
    )
    (net (code "115") (name "unconnected-(U3-R{slash}W-Pad16)") (class "Default")
      (node (ref "U3") (pin "16") (pinfunction "R/W_16") (pintype "input"))
    )
    (net (code "116") (name "unconnected-(U4-D3-Pad21)") (class "Default")
      (node (ref "U4") (pin "21") (pinfunction "D3_21") (pintype "bidirectional"))
    )
    (net (code "117") (name "unconnected-(U4-D4-Pad22)") (class "Default")
      (node (ref "U4") (pin "22") (pinfunction "D4_22") (pintype "bidirectional"))
    )
    (net (code "118") (name "unconnected-(U4-D5-Pad23)") (class "Default")
      (node (ref "U4") (pin "23") (pinfunction "D5_23") (pintype "bidirectional"))
    )
    (net (code "119") (name "unconnected-(U4-D6-Pad24)") (class "Default")
      (node (ref "U4") (pin "24") (pinfunction "D6_24") (pintype "bidirectional"))
    )
    (net (code "120") (name "unconnected-(U4-D7-Pad25)") (class "Default")
      (node (ref "U4") (pin "25") (pinfunction "D7_25") (pintype "bidirectional"))
    )
    (net (code "121") (name "unconnected-(U4-E{slash}RD-Pad17)") (class "Default")
      (node (ref "U4") (pin "17") (pinfunction "E/RD_17") (pintype "input"))
    )
    (net (code "122") (name "unconnected-(U4-NC-Pad7)") (class "Default")
      (node (ref "U4") (pin "7") (pinfunction "NC_7") (pintype "no_connect"))
    )
    (net (code "123") (name "unconnected-(U4-R{slash}W-Pad16)") (class "Default")
      (node (ref "U4") (pin "16") (pinfunction "R/W_16") (pintype "input"))
    )
  )
)
